# karmanDB_sensors1.net
KiCad netlist of a schematic drawn in Altium Designer
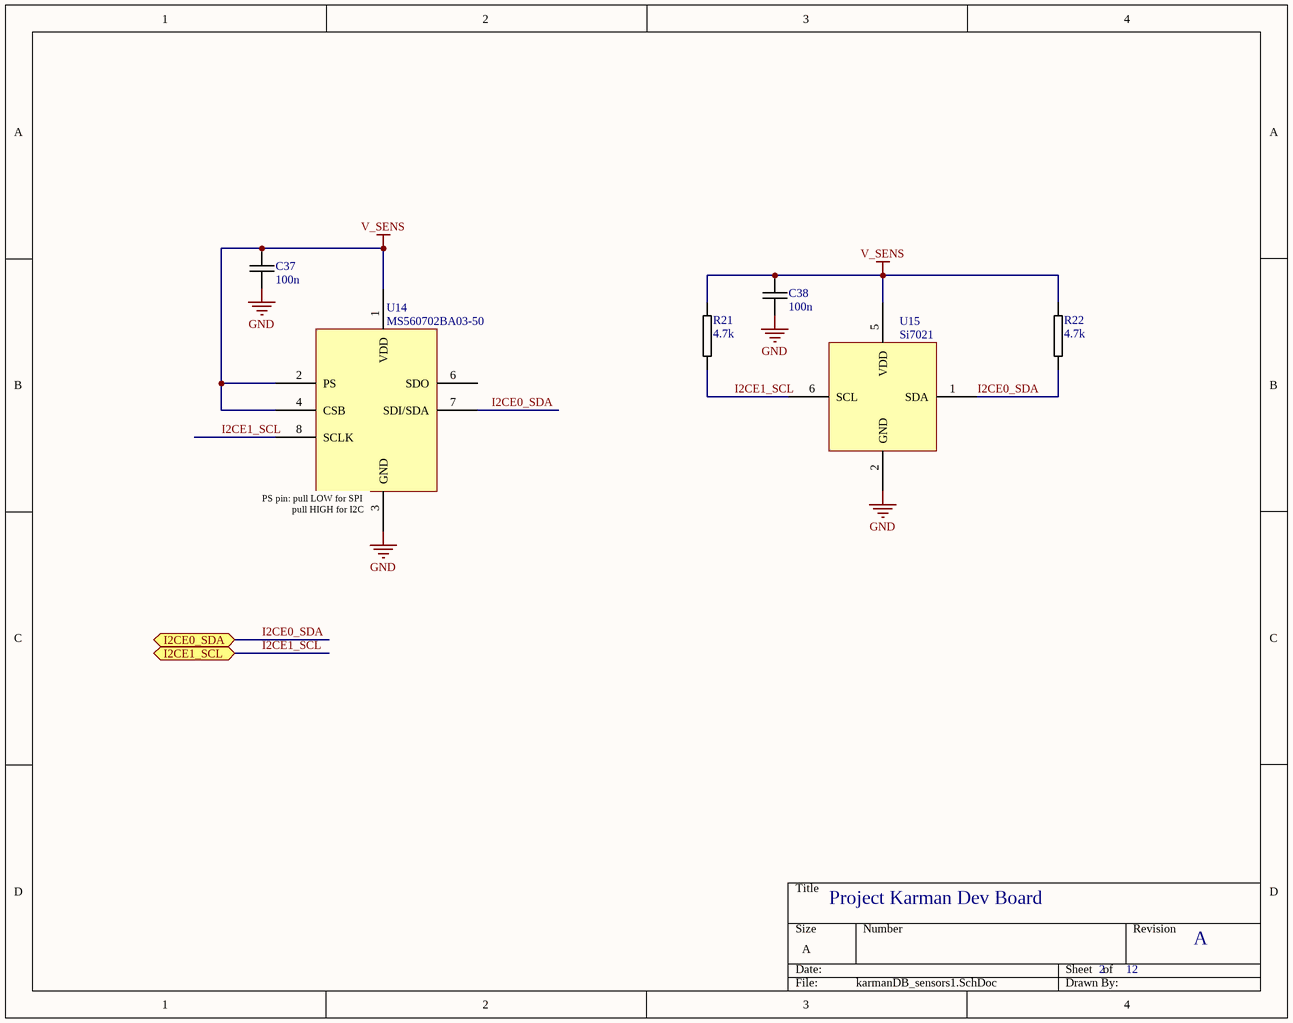
[diagram p0: karmanDB_sensors1.SchDoc]

(export (version "E")
  (design (tool "Eeschema 10.0.6"))
  (components
    (comp (ref "C37")
      (value "100n")
      (footprint "MURATA_GRM_0603")
      (description "CAP CER 0.1UF 16V 10% X7R 0603")
      (fields
        (field (name "MANUFACTURER") "Murata Electronics North America")
        (field (name "MANUFACTURER PART NUMBER") "GRM188R71C104KA01D")
      )
      (libsource (lib "project_symbols") (part "CAP_MURATA_GRM188R71C104KA01D"))
    )
    (comp (ref "C38")
      (value "100n")
      (footprint "MURATA_GRM_0603")
      (description "CAP CER 0.1UF 16V 10% X7R 0603")
      (fields
        (field (name "MANUFACTURER") "Murata Electronics North America")
        (field (name "MANUFACTURER PART NUMBER") "GRM188R71C104KA01D")
      )
      (libsource (lib "project_symbols") (part "CAP_MURATA_GRM188R71C104KA01D"))
    )
    (comp (ref "R21")
      (value "4.7k")
      (footprint "PANASONIC_ERJ2R_SERIES")
      (description "RES SMD 4.7K OHM 1% 1/10W 0402")
      (fields
        (field (name "MANUFACTURER") "Panasonic Electronic Components")
        (field (name "MANUFACTURER PART NUMBER") "ERJ-2RKF4701X")
      )
      (libsource (lib "project_symbols") (part "RES_PANASONIC_ERJ-2RKF4701X"))
    )
    (comp (ref "R22")
      (value "4.7k")
      (footprint "PANASONIC_ERJ2R_SERIES")
      (description "RES SMD 4.7K OHM 1% 1/10W 0402")
      (fields
        (field (name "MANUFACTURER") "Panasonic Electronic Components")
        (field (name "MANUFACTURER PART NUMBER") "ERJ-2RKF4701X")
      )
      (libsource (lib "project_symbols") (part "RES_PANASONIC_ERJ-2RKF4701X"))
    )
    (comp (ref "U14")
      (value "MS560702BA03-50")
      (footprint "8 MS560702BA03-50")
      (description "BAROMETRIC PRESSURE SENSOR")
      (fields (field (name "MANUFACTURER") "TE Connectivity Measurement Specialties"))
      (libsource (lib "karman_pcb") (part "MS560702BA03-50"))
    )
    (comp (ref "U15")
      (value "Si7021")
      (footprint "7 Si7021-A20")
      (description "IC TEMP SENSOR RH 3% 6DFN")
      (fields
        (field (name "MANUFACTURER") "Silicon Labs")
        (field (name "MANUFACTURER PART NUMBER") "SI7021-A20-GM")
      )
      (libsource (lib "karman_pcb") (part "SI7021-A20-GM"))
    )
  )
  (nets
    (net (code "1") (name "/I2CE0_SDA") (class "Default")
      (node (ref "R22") (pin "2") (pintype "passive"))
      (node (ref "U14") (pin "7") (pinfunction "SDI/SDA_7") (pintype "passive"))
      (node (ref "U15") (pin "1") (pinfunction "SDA_1") (pintype "passive"))
    )
    (net (code "2") (name "/I2CE1_SCL") (class "Default")
      (node (ref "R21") (pin "2") (pintype "passive"))
      (node (ref "U14") (pin "8") (pinfunction "SCLK_8") (pintype "passive"))
      (node (ref "U15") (pin "6") (pinfunction "SCL_6") (pintype "passive"))
    )
    (net (code "3") (name "GND") (class "Default")
      (node (ref "C37") (pin "2") (pintype "passive"))
      (node (ref "C38") (pin "2") (pintype "passive"))
      (node (ref "U14") (pin "3") (pinfunction "GND_3") (pintype "passive"))
      (node (ref "U15") (pin "2") (pinfunction "GND_2") (pintype "passive"))
    )
    (net (code "4") (name "V_SENS") (class "Default")
      (node (ref "C37") (pin "1") (pintype "passive"))
      (node (ref "C38") (pin "1") (pintype "passive"))
      (node (ref "R21") (pin "1") (pintype "passive"))
      (node (ref "R22") (pin "1") (pintype "passive"))
      (node (ref "U14") (pin "1") (pinfunction "VDD_1") (pintype "passive"))
      (node (ref "U14") (pin "2") (pinfunction "PS_2") (pintype "passive"))
      (node (ref "U14") (pin "4") (pinfunction "CSB_4") (pintype "passive"))
      (node (ref "U15") (pin "5") (pinfunction "VDD_5") (pintype "passive"))
    )
    (net (code "5") (name "unconnected-(U14-SDO-Pad6)") (class "Default")
      (node (ref "U14") (pin "6") (pinfunction "SDO_6") (pintype "passive"))
    )
    (net (code "6") (name "unconnected-(U15-DNC-Pad3)") (class "Default")
      (node (ref "U15") (pin "3") (pinfunction "DNC_3") (pintype "passive"))
    )
    (net (code "7") (name "unconnected-(U15-DNC-Pad4)") (class "Default")
      (node (ref "U15") (pin "4") (pinfunction "DNC_4") (pintype "passive"))
    )
  )
)
